# BUF_ADC.net
KiCad netlist of a schematic drawn in Altium Designer
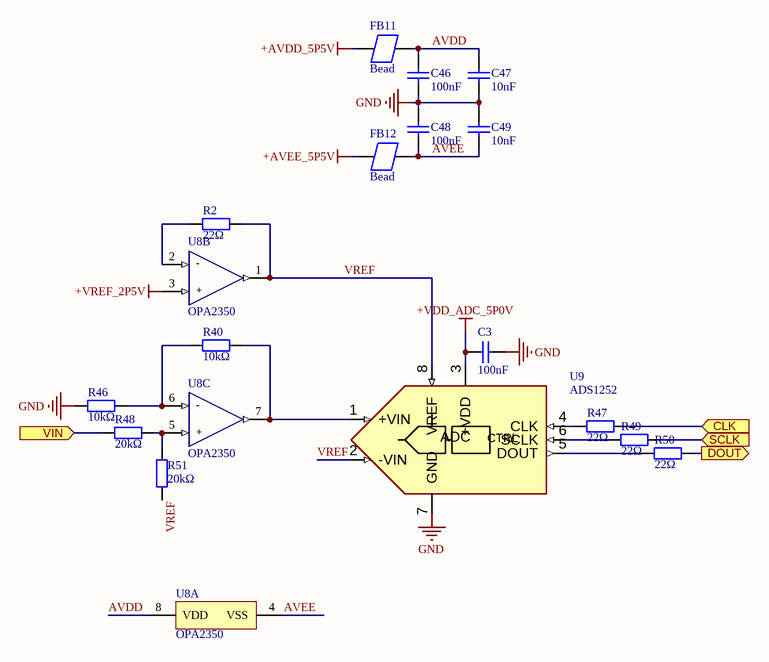
[diagram p0: BUF_ADC.SchDoc]

(export (version "E")
  (design (tool "Eeschema 10.0.6"))
  (components
    (comp (ref "C3")
      (value "100nF")
      (footprint "0603_C")
      (description "贴片电容")
      (libsource (lib "Miscellaneous Devices LC") (part "0603 100nF (104) 10% 50V"))
    )
    (comp (ref "C46")
      (value "100nF")
      (footprint "0603_C")
      (description "贴片电容")
      (libsource (lib "Miscellaneous Devices LC") (part "0603 100nF (104) 10% 50V"))
    )
    (comp (ref "C47")
      (value "10nF")
      (footprint "0603_C")
      (description "贴片电容")
      (libsource (lib "Miscellaneous Devices LC") (part "0603 10nF (103) 10% 50V"))
    )
    (comp (ref "C48")
      (value "100nF")
      (footprint "0603_C")
      (description "贴片电容")
      (libsource (lib "Miscellaneous Devices LC") (part "0603 100nF (104) 10% 50V"))
    )
    (comp (ref "C49")
      (value "10nF")
      (footprint "0603_C")
      (description "贴片电容")
      (libsource (lib "Miscellaneous Devices LC") (part "0603 10nF (103) 10% 50V"))
    )
    (comp (ref "FB11") (value "Bead") (footprint "0805_L") (libsource (lib "OlvkLib") (part "Bead")))
    (comp (ref "FB12") (value "Bead") (footprint "0805_L") (libsource (lib "OlvkLib") (part "Bead")))
    (comp (ref "R2")
      (value "22Ω")
      (footprint "0603_R")
      (description "贴片电阻")
      (libsource (lib "Miscellaneous Devices LC") (part "0603 22Ω (22R0) 1%"))
    )
    (comp (ref "R40")
      (value "10kΩ")
      (footprint "0603_R")
      (description "贴片电阻")
      (libsource (lib "Miscellaneous Devices LC") (part "0603 10KΩ (1002) 1%"))
    )
    (comp (ref "R46")
      (value "10kΩ")
      (footprint "0603_R")
      (description "贴片电阻")
      (libsource (lib "Miscellaneous Devices LC") (part "0603 10KΩ (1002) 1%"))
    )
    (comp (ref "R47")
      (value "22Ω")
      (footprint "0603_R")
      (description "贴片电阻")
      (libsource (lib "Miscellaneous Devices LC") (part "0603 22Ω (22R0) 1%"))
    )
    (comp (ref "R48")
      (value "20kΩ")
      (footprint "0603_R")
      (description "贴片电阻")
      (libsource (lib "Miscellaneous Devices LC") (part "0603 10KΩ (1002) 1%"))
    )
    (comp (ref "R49")
      (value "22Ω")
      (footprint "0603_R")
      (description "贴片电阻")
      (libsource (lib "Miscellaneous Devices LC") (part "0603 22Ω (22R0) 1%"))
    )
    (comp (ref "R50")
      (value "22Ω")
      (footprint "0603_R")
      (description "贴片电阻")
      (libsource (lib "Miscellaneous Devices LC") (part "0603 22Ω (22R0) 1%"))
    )
    (comp (ref "R51")
      (value "20kΩ")
      (footprint "0603_R")
      (description "贴片电阻")
      (libsource (lib "") (part "0603 10KΩ (1002) 1%_1"))
    )
    (comp (ref "U8")
      (value "OPA2350")
      (footprint "SOIC127P600X175-8M")
      (description "10MHz RRIO Zero-Drift 5.5V")
      (libsource (lib "OlvkLib") (part "OPA2350"))
    )
    (comp (ref "U9")
      (value "ADS1252")
      (footprint "SOIC127P600X175-8M")
      (libsource (lib "OlvkLib") (part "ADS1252"))
    )
  )
  (nets
    (net (code "1") (name "+AVDD_5P5V") (class "Default")
      (node (ref "FB11") (pin "1") (pinfunction "1_1") (pintype "passive"))
    )
    (net (code "2") (name "+AVEE_5P5V") (class "Default")
      (node (ref "FB12") (pin "1") (pinfunction "1_1") (pintype "passive"))
    )
    (net (code "3") (name "+VDD_ADC_5P0V") (class "Default")
      (node (ref "C3") (pin "1") (pinfunction "1_1") (pintype "passive"))
      (node (ref "U9") (pin "3") (pinfunction "+VDD_3") (pintype "power_in"))
    )
    (net (code "4") (name "+VREF_2P5V") (class "Default")
      (node (ref "U8") (pin "3") (pinfunction "+INA_3") (pintype "input"))
    )
    (net (code "5") (name "/AVDD") (class "Default")
      (node (ref "C46") (pin "2") (pinfunction "2_2") (pintype "passive"))
      (node (ref "C47") (pin "2") (pinfunction "2_2") (pintype "passive"))
      (node (ref "FB11") (pin "2") (pinfunction "2_2") (pintype "passive"))
      (node (ref "U8") (pin "8") (pinfunction "VDD_8") (pintype "power_in"))
    )
    (net (code "6") (name "/AVEE") (class "Default")
      (node (ref "C48") (pin "2") (pinfunction "2_2") (pintype "passive"))
      (node (ref "C49") (pin "2") (pinfunction "2_2") (pintype "passive"))
      (node (ref "FB12") (pin "2") (pinfunction "2_2") (pintype "passive"))
      (node (ref "U8") (pin "4") (pinfunction "VSS_4") (pintype "power_in"))
    )
    (net (code "7") (name "/CLK") (class "Default")
      (node (ref "R47") (pin "2") (pinfunction "2_2") (pintype "passive"))
    )
    (net (code "8") (name "/DOUT") (class "Default")
      (node (ref "R50") (pin "2") (pinfunction "2_2") (pintype "passive"))
    )
    (net (code "9") (name "/SCLK") (class "Default")
      (node (ref "R49") (pin "2") (pinfunction "2_2") (pintype "passive"))
    )
    (net (code "10") (name "/VIN") (class "Default")
      (node (ref "R48") (pin "1") (pinfunction "1_1") (pintype "passive"))
    )
    (net (code "11") (name "/VREF") (class "Default")
      (node (ref "R2") (pin "2") (pinfunction "2_2") (pintype "passive"))
      (node (ref "R51") (pin "2") (pinfunction "2_2") (pintype "passive"))
      (node (ref "U8") (pin "1") (pinfunction "OUTA_1") (pintype "output"))
      (node (ref "U9") (pin "2") (pinfunction "-VIN_2") (pintype "input"))
      (node (ref "U9") (pin "8") (pinfunction "VREF_8") (pintype "input"))
    )
    (net (code "12") (name "GND") (class "Default")
      (node (ref "C3") (pin "2") (pinfunction "2_2") (pintype "passive"))
      (node (ref "C46") (pin "1") (pinfunction "1_1") (pintype "passive"))
      (node (ref "C47") (pin "1") (pinfunction "1_1") (pintype "passive"))
      (node (ref "C48") (pin "1") (pinfunction "1_1") (pintype "passive"))
      (node (ref "C49") (pin "1") (pinfunction "1_1") (pintype "passive"))
      (node (ref "R46") (pin "1") (pinfunction "1_1") (pintype "passive"))
      (node (ref "U9") (pin "7") (pinfunction "GND_7") (pintype "power_in"))
    )
    (net (code "13") (name "Net-(U8B--INA)") (class "Default")
      (node (ref "R2") (pin "1") (pinfunction "1_1") (pintype "passive"))
      (node (ref "U8") (pin "2") (pinfunction "-INA_2") (pintype "input"))
    )
    (net (code "14") (name "Net-(U8C-+INB)") (class "Default")
      (node (ref "R48") (pin "2") (pinfunction "2_2") (pintype "passive"))
      (node (ref "R51") (pin "1") (pinfunction "1_1") (pintype "passive"))
      (node (ref "U8") (pin "5") (pinfunction "+INB_5") (pintype "input"))
    )
    (net (code "15") (name "Net-(U8C--INB)") (class "Default")
      (node (ref "R40") (pin "1") (pinfunction "1_1") (pintype "passive"))
      (node (ref "R46") (pin "2") (pinfunction "2_2") (pintype "passive"))
      (node (ref "U8") (pin "6") (pinfunction "-INB_6") (pintype "input"))
    )
    (net (code "16") (name "Net-(U8C-OUTB)") (class "Default")
      (node (ref "R40") (pin "2") (pinfunction "2_2") (pintype "passive"))
      (node (ref "U8") (pin "7") (pinfunction "OUTB_7") (pintype "output"))
      (node (ref "U9") (pin "1") (pinfunction "+VIN_1") (pintype "input"))
    )
    (net (code "17") (name "Net-(U9-CLK)") (class "Default")
      (node (ref "R47") (pin "1") (pinfunction "1_1") (pintype "passive"))
      (node (ref "U9") (pin "4") (pinfunction "CLK_4") (pintype "input"))
    )
    (net (code "18") (name "Net-(U9-DOUT)") (class "Default")
      (node (ref "R50") (pin "1") (pinfunction "1_1") (pintype "passive"))
      (node (ref "U9") (pin "5") (pinfunction "DOUT_5") (pintype "output"))
    )
    (net (code "19") (name "Net-(U9-SCLK)") (class "Default")
      (node (ref "R49") (pin "1") (pinfunction "1_1") (pintype "passive"))
      (node (ref "U9") (pin "6") (pinfunction "SCLK_6") (pintype "input"))
    )
  )
)
